# USB_to_UART.net
KiCad netlist of a schematic drawn in Altium Designer
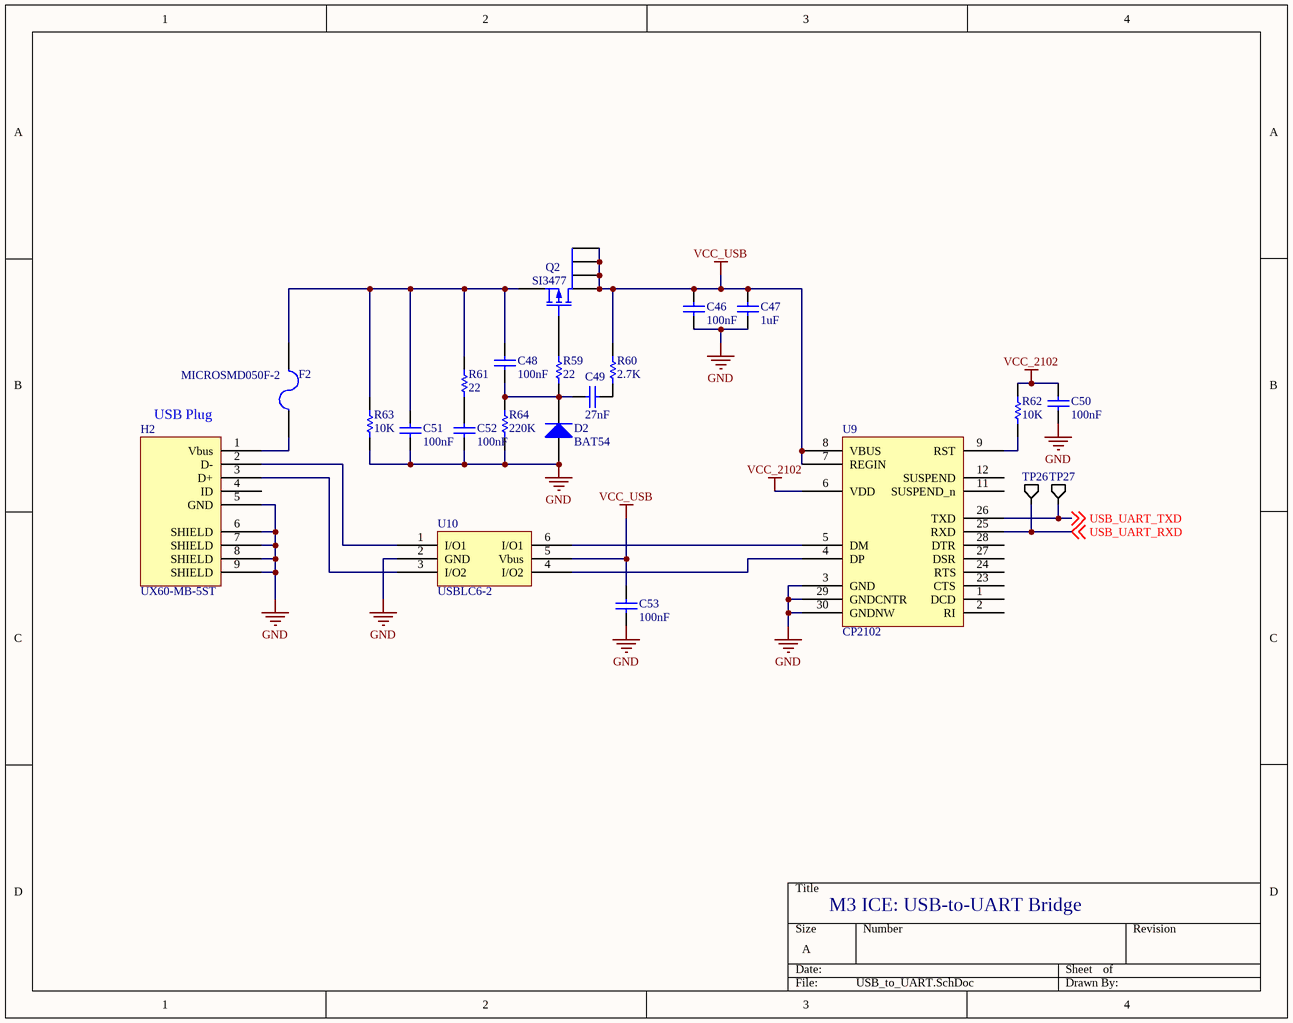
[diagram p0: USB_to_UART.SchDoc]

(export (version "E")
  (design (tool "Eeschema 10.0.6"))
  (components
    (comp (ref "C46")
      (value "100nF")
      (footprint "1608[0603]")
      (description "Capacitor (Semiconductor SIM Model)")
      (fields (field (name "Comment") "Cap Semi") (field (name "PUBLISHER") "Altium Limited"))
      (libsource (lib "Miscellaneous Devices") (part "Cap Semi"))
    )
    (comp (ref "C47")
      (value "1uF")
      (footprint "1608[0603]")
      (description "Capacitor (Semiconductor SIM Model)")
      (fields (field (name "Comment") "Cap Semi") (field (name "PUBLISHER") "Altium Limited"))
      (libsource (lib "Miscellaneous Devices") (part "Cap Semi"))
    )
    (comp (ref "C48")
      (value "100nF")
      (footprint "1608[0603]")
      (description "Capacitor (Semiconductor SIM Model)")
      (fields (field (name "Comment") "Cap Semi") (field (name "PUBLISHER") "Altium Limited"))
      (libsource (lib "Miscellaneous Devices") (part "Cap Semi"))
    )
    (comp (ref "C49")
      (value "27nF")
      (footprint "1608[0603]")
      (description "Capacitor (Semiconductor SIM Model)")
      (fields (field (name "Comment") "Cap Semi") (field (name "PUBLISHER") "Altium Limited"))
      (libsource (lib "Miscellaneous Devices") (part "Cap Semi"))
    )
    (comp (ref "C50")
      (value "100nF")
      (footprint "1608[0603]")
      (description "Capacitor (Semiconductor SIM Model)")
      (fields (field (name "Comment") "Cap Semi") (field (name "PUBLISHER") "Altium Limited"))
      (libsource (lib "Miscellaneous Devices") (part "Cap Semi"))
    )
    (comp (ref "C51")
      (value "100nF")
      (footprint "1608[0603]")
      (description "Capacitor (Semiconductor SIM Model)")
      (fields (field (name "Comment") "Cap Semi") (field (name "PUBLISHER") "Altium Limited"))
      (libsource (lib "Miscellaneous Devices") (part "Cap Semi"))
    )
    (comp (ref "C52")
      (value "100nF")
      (footprint "1608[0603]")
      (description "Capacitor (Semiconductor SIM Model)")
      (fields (field (name "Comment") "Cap Semi") (field (name "PUBLISHER") "Altium Limited"))
      (libsource (lib "Miscellaneous Devices") (part "Cap Semi"))
    )
    (comp (ref "C53")
      (value "100nF")
      (footprint "1608[0603]")
      (description "Capacitor (Semiconductor SIM Model)")
      (fields (field (name "Comment") "Cap Semi") (field (name "PUBLISHER") "Altium Limited"))
      (libsource (lib "Miscellaneous Devices") (part "Cap Semi"))
    )
    (comp (ref "D2")
      (value "BAT54")
      (footprint "SOT-23_N")
      (description "Low-Loss RF Switching Diode")
      (fields (field (name "PUBLISHER") "Altium Limited"))
      (libsource (lib "Miscellaneous Devices") (part "Diode BAT18"))
    )
    (comp (ref "F2")
      (value "MICROSMD050F-2")
      (footprint "1210")
      (description "POLYSWITCH 0.50A RESET FUSE SMD")
      (fields (field (name "PUBLISHER") "Altium Limited"))
      (libsource (lib "M3") (part "Fuse MICROSMD050F-2"))
    )
    (comp (ref "H2")
      (value "UX60-MB-5ST")
      (footprint "USB Mini-B")
      (description "USB mini-B")
      (libsource (lib "M3") (part "UX60-MB-5ST"))
    )
    (comp (ref "Q2")
      (value "SI3477")
      (footprint "TSOP-6")
      (description "P-Channel MOSFET")
      (fields (field (name "PUBLISHER") "Altium Limited"))
      (libsource (lib "M3") (part "SI3477"))
    )
    (comp (ref "R59")
      (value "22")
      (footprint "0603")
      (description "Semiconductor Resistor")
      (fields (field (name "Comment") "Res Chip") (field (name "PUBLISHER") "Altium Limited"))
      (libsource (lib "M3") (part "Res Chip"))
    )
    (comp (ref "R60")
      (value "2.7K")
      (footprint "0603")
      (description "Semiconductor Resistor")
      (fields (field (name "Comment") "Res Chip") (field (name "PUBLISHER") "Altium Limited"))
      (libsource (lib "M3") (part "Res Chip"))
    )
    (comp (ref "R61")
      (value "22")
      (footprint "0603")
      (description "Semiconductor Resistor")
      (fields (field (name "Comment") "Res Chip") (field (name "PUBLISHER") "Altium Limited"))
      (libsource (lib "M3") (part "Res Chip"))
    )
    (comp (ref "R62")
      (value "10K")
      (footprint "0603")
      (description "Semiconductor Resistor")
      (fields (field (name "Comment") "Res Chip") (field (name "PUBLISHER") "Altium Limited"))
      (libsource (lib "M3") (part "Res Chip"))
    )
    (comp (ref "R63")
      (value "10K")
      (footprint "0603")
      (description "Semiconductor Resistor")
      (fields (field (name "Comment") "Res Chip") (field (name "PUBLISHER") "Altium Limited"))
      (libsource (lib "M3") (part "Res Chip"))
    )
    (comp (ref "R64")
      (value "220K")
      (footprint "0603")
      (description "Semiconductor Resistor")
      (fields (field (name "Comment") "Res Chip") (field (name "PUBLISHER") "Altium Limited"))
      (libsource (lib "M3") (part "Res Chip"))
    )
    (comp (ref "TP26") (value "TP") (footprint "TP") (libsource (lib "M3") (part "TP")))
    (comp (ref "TP27") (value "TP") (footprint "TP") (libsource (lib "M3") (part "TP")))
    (comp (ref "U9") (value "CP2102") (footprint "QFN-28") (libsource (lib "M3") (part "CP2102")))
    (comp (ref "U10")
      (value "USBLC6-2")
      (footprint "SOT23-6_L")
      (description "USB ESD Protection")
      (libsource (lib "M3") (part "USBLC6-2"))
    )
  )
  (nets
    (net (code "1") (name "GND") (class "Default")
      (node (ref "C46") (pin "1") (pinfunction "1_1") (pintype "passive"))
      (node (ref "C47") (pin "1") (pinfunction "1_1") (pintype "passive"))
      (node (ref "C50") (pin "1") (pinfunction "1_1") (pintype "passive"))
      (node (ref "C51") (pin "1") (pinfunction "1_1") (pintype "passive"))
      (node (ref "C52") (pin "1") (pinfunction "1_1") (pintype "passive"))
      (node (ref "C53") (pin "1") (pinfunction "1_1") (pintype "passive"))
      (node (ref "D2") (pin "1") (pinfunction "A_1") (pintype "passive"))
      (node (ref "H2") (pin "5") (pinfunction "GND_5") (pintype "passive"))
      (node (ref "H2") (pin "6") (pinfunction "SHIELD_6") (pintype "passive"))
      (node (ref "H2") (pin "7") (pinfunction "SHIELD_7") (pintype "passive"))
      (node (ref "H2") (pin "8") (pinfunction "SHIELD_8") (pintype "passive"))
      (node (ref "H2") (pin "9") (pinfunction "SHIELD_9") (pintype "passive"))
      (node (ref "R63") (pin "1") (pinfunction "1_1") (pintype "passive"))
      (node (ref "R64") (pin "1") (pinfunction "1_1") (pintype "passive"))
      (node (ref "U10") (pin "2") (pinfunction "GND_2") (pintype "passive"))
      (node (ref "U9") (pin "29") (pinfunction "GNDCNTR_29") (pintype "passive"))
      (node (ref "U9") (pin "3") (pinfunction "GND_3") (pintype "passive"))
      (node (ref "U9") (pin "30") (pinfunction "GNDNW_30") (pintype "passive"))
    )
    (net (code "2") (name "Net-(C49-Pad1)") (class "Default")
      (node (ref "C49") (pin "1") (pinfunction "1_1") (pintype "passive"))
      (node (ref "R60") (pin "1") (pinfunction "1_1") (pintype "passive"))
    )
    (net (code "3") (name "Net-(C52-Pad2)") (class "Default")
      (node (ref "C52") (pin "2") (pinfunction "2_2") (pintype "passive"))
      (node (ref "R61") (pin "1") (pinfunction "1_1") (pintype "passive"))
    )
    (net (code "4") (name "Net-(D2-K)") (class "Default")
      (node (ref "C48") (pin "1") (pinfunction "1_1") (pintype "passive"))
      (node (ref "C49") (pin "2") (pinfunction "2_2") (pintype "passive"))
      (node (ref "D2") (pin "3") (pinfunction "K_3") (pintype "passive"))
      (node (ref "R59") (pin "1") (pinfunction "1_1") (pintype "passive"))
      (node (ref "R64") (pin "2") (pinfunction "2_2") (pintype "passive"))
    )
    (net (code "5") (name "Net-(H2-D+)") (class "Default")
      (node (ref "H2") (pin "3") (pinfunction "D+_3") (pintype "passive"))
      (node (ref "U10") (pin "3") (pinfunction "I/O2_3") (pintype "passive"))
    )
    (net (code "6") (name "Net-(H2-D-)") (class "Default")
      (node (ref "H2") (pin "2") (pinfunction "D-_2") (pintype "passive"))
      (node (ref "U10") (pin "1") (pinfunction "I/O1_1") (pintype "passive"))
    )
    (net (code "7") (name "Net-(H2-Vbus)") (class "Default")
      (node (ref "F2") (pin "1") (pinfunction "1_1") (pintype "passive"))
      (node (ref "H2") (pin "1") (pinfunction "Vbus_1") (pintype "passive"))
    )
    (net (code "8") (name "Net-(Q2-G)") (class "Default")
      (node (ref "Q2") (pin "3") (pinfunction "G_3") (pintype "passive"))
      (node (ref "R59") (pin "2") (pinfunction "2_2") (pintype "passive"))
    )
    (net (code "9") (name "Net-(Q2-S)") (class "Default")
      (node (ref "C48") (pin "2") (pinfunction "2_2") (pintype "passive"))
      (node (ref "C51") (pin "2") (pinfunction "2_2") (pintype "passive"))
      (node (ref "F2") (pin "2") (pinfunction "2_2") (pintype "passive"))
      (node (ref "Q2") (pin "4") (pinfunction "S_4") (pintype "passive"))
      (node (ref "R61") (pin "2") (pinfunction "2_2") (pintype "passive"))
      (node (ref "R63") (pin "2") (pinfunction "2_2") (pintype "passive"))
    )
    (net (code "10") (name "Net-(U9-DM)") (class "Default")
      (node (ref "U10") (pin "6") (pinfunction "I/O1_6") (pintype "passive"))
      (node (ref "U9") (pin "5") (pinfunction "DM_5") (pintype "passive"))
    )
    (net (code "11") (name "Net-(U9-DP)") (class "Default")
      (node (ref "U10") (pin "4") (pinfunction "I/O2_4") (pintype "passive"))
      (node (ref "U9") (pin "4") (pinfunction "DP_4") (pintype "passive"))
    )
    (net (code "12") (name "Net-(U9-RST)") (class "Default")
      (node (ref "R62") (pin "1") (pinfunction "1_1") (pintype "passive"))
      (node (ref "U9") (pin "9") (pinfunction "RST_9") (pintype "passive"))
    )
    (net (code "13") (name "USB_UART_RXD") (class "Default")
      (node (ref "TP26") (pin "1") (pinfunction "A_1") (pintype "passive"))
      (node (ref "U9") (pin "25") (pinfunction "RXD_25") (pintype "passive"))
    )
    (net (code "14") (name "USB_UART_TXD") (class "Default")
      (node (ref "TP27") (pin "1") (pinfunction "A_1") (pintype "passive"))
      (node (ref "U9") (pin "26") (pinfunction "TXD_26") (pintype "passive"))
    )
    (net (code "15") (name "VCC_2102") (class "Default")
      (node (ref "C50") (pin "2") (pinfunction "2_2") (pintype "passive"))
      (node (ref "R62") (pin "2") (pinfunction "2_2") (pintype "passive"))
      (node (ref "U9") (pin "6") (pinfunction "VDD_6") (pintype "passive"))
    )
    (net (code "16") (name "VCC_USB") (class "Default")
      (node (ref "C46") (pin "2") (pinfunction "2_2") (pintype "passive"))
      (node (ref "C47") (pin "2") (pinfunction "2_2") (pintype "passive"))
      (node (ref "C53") (pin "2") (pinfunction "2_2") (pintype "passive"))
      (node (ref "Q2") (pin "1") (pinfunction "D_1") (pintype "passive"))
      (node (ref "Q2") (pin "2") (pinfunction "D_2") (pintype "passive"))
      (node (ref "Q2") (pin "5") (pinfunction "D_5") (pintype "passive"))
      (node (ref "Q2") (pin "6") (pinfunction "D_6") (pintype "passive"))
      (node (ref "R60") (pin "2") (pinfunction "2_2") (pintype "passive"))
      (node (ref "U10") (pin "5") (pinfunction "Vbus_5") (pintype "passive"))
      (node (ref "U9") (pin "7") (pinfunction "REGIN_7") (pintype "passive"))
      (node (ref "U9") (pin "8") (pinfunction "VBUS_8") (pintype "passive"))
    )
    (net (code "17") (name "unconnected-(H2-ID-Pad4)") (class "Default")
      (node (ref "H2") (pin "4") (pinfunction "ID_4") (pintype "passive"))
    )
    (net (code "18") (name "unconnected-(U9-CTS-Pad23)") (class "Default")
      (node (ref "U9") (pin "23") (pinfunction "CTS_23") (pintype "passive"))
    )
    (net (code "19") (name "unconnected-(U9-DCD-Pad1)") (class "Default")
      (node (ref "U9") (pin "1") (pinfunction "DCD_1") (pintype "passive"))
    )
    (net (code "20") (name "unconnected-(U9-DSR-Pad27)") (class "Default")
      (node (ref "U9") (pin "27") (pinfunction "DSR_27") (pintype "passive"))
    )
    (net (code "21") (name "unconnected-(U9-DTR-Pad28)") (class "Default")
      (node (ref "U9") (pin "28") (pinfunction "DTR_28") (pintype "passive"))
    )
    (net (code "22") (name "unconnected-(U9-RI-Pad2)") (class "Default")
      (node (ref "U9") (pin "2") (pinfunction "RI_2") (pintype "passive"))
    )
    (net (code "23") (name "unconnected-(U9-RTS-Pad24)") (class "Default")
      (node (ref "U9") (pin "24") (pinfunction "RTS_24") (pintype "passive"))
    )
    (net (code "24") (name "unconnected-(U9-SUSPEND-Pad12)") (class "Default")
      (node (ref "U9") (pin "12") (pinfunction "SUSPEND_12") (pintype "passive"))
    )
    (net (code "25") (name "unconnected-(U9-SUSPEND_n-Pad11)") (class "Default")
      (node (ref "U9") (pin "11") (pinfunction "SUSPEND_n_11") (pintype "passive"))
    )
  )
)
